# atmega_copier.net
KiCad netlist of a schematic drawn in EAGLE
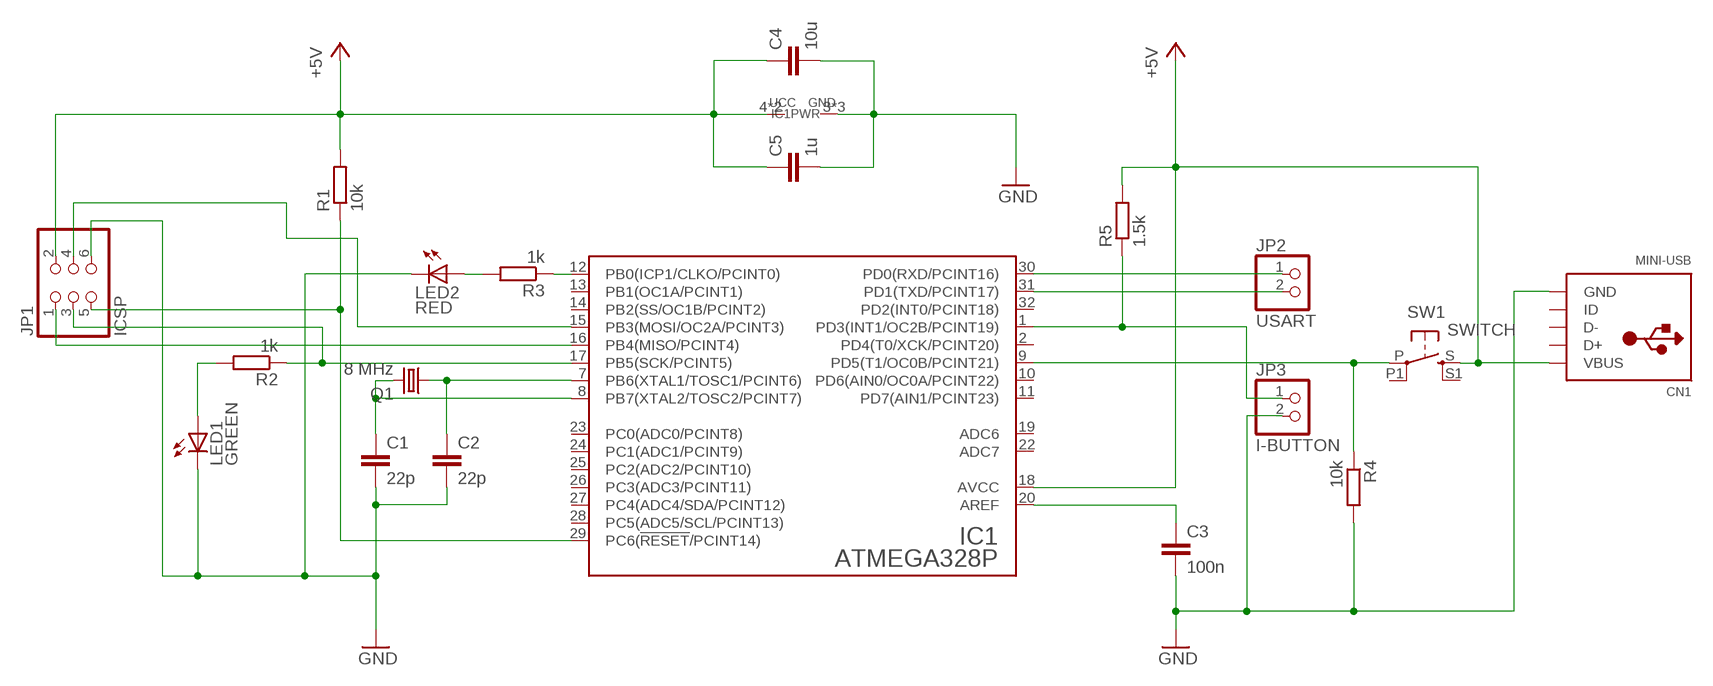
[diagram p0: schematic, sheet 1]

(export (version "E")
  (design (tool "Eeschema 10.0.6"))
  (components
    (comp (ref "C1")
      (value "22p")
      (footprint "eagle-import:C0805")
      (libsource (lib "eagle-import") (part "C-EUC0805"))
    )
    (comp (ref "C2")
      (value "22p")
      (footprint "eagle-import:C0805")
      (libsource (lib "eagle-import") (part "C-EUC0805"))
    )
    (comp (ref "C3")
      (value "100n")
      (footprint "eagle-import:C0805")
      (libsource (lib "eagle-import") (part "C-EUC0805"))
    )
    (comp (ref "C4")
      (value "10u")
      (footprint "eagle-import:C0805")
      (libsource (lib "eagle-import") (part "C-EUC0805"))
    )
    (comp (ref "C5")
      (value "1u")
      (footprint "eagle-import:C0805")
      (libsource (lib "eagle-import") (part "C-EUC0805"))
    )
    (comp (ref "CN1")
      (value "MINI-USB")
      (footprint "eagle-import:USB-MINIB")
      (libsource (lib "eagle-import") (part "USBMINIB"))
    )
    (comp (ref "IC1")
      (value "ATMEGA328P")
      (footprint "eagle-import:TQFP32-08")
      (libsource (lib "eagle-import") (part "ATMEGA48/88/168/328-AU"))
    )
    (comp (ref "JP1")
      (value "ICSP")
      (footprint "eagle-import:2X03")
      (libsource (lib "eagle-import") (part "PINHD-2X3"))
    )
    (comp (ref "JP2")
      (value "USART")
      (footprint "eagle-import:1X02")
      (libsource (lib "eagle-import") (part "PINHD-1X2"))
    )
    (comp (ref "JP3")
      (value "I-BUTTON")
      (footprint "eagle-import:1X02")
      (libsource (lib "eagle-import") (part "PINHD-1X2"))
    )
    (comp (ref "LED1")
      (value "GREEN")
      (footprint "eagle-import:SML0805")
      (libsource (lib "eagle-import") (part "LEDSML0805"))
    )
    (comp (ref "LED2")
      (value "RED")
      (footprint "eagle-import:SML0805")
      (libsource (lib "eagle-import") (part "LEDSML0805"))
    )
    (comp (ref "Q1")
      (value "8 MHz")
      (footprint "eagle-import:HC49UP")
      (libsource (lib "eagle-import") (part "CRYSTALHC49UP"))
    )
    (comp (ref "R1")
      (value "10k")
      (footprint "eagle-import:R0805")
      (libsource (lib "eagle-import") (part "R-EU_R0805"))
    )
    (comp (ref "R2")
      (value "1k")
      (footprint "eagle-import:R0805")
      (libsource (lib "eagle-import") (part "R-EU_R0805"))
    )
    (comp (ref "R3")
      (value "1k")
      (footprint "eagle-import:R0805")
      (libsource (lib "eagle-import") (part "R-EU_R0805"))
    )
    (comp (ref "R4")
      (value "10k")
      (footprint "eagle-import:R0805")
      (libsource (lib "eagle-import") (part "R-EU_R0805"))
    )
    (comp (ref "R5")
      (value "1.5k")
      (footprint "eagle-import:R0805")
      (libsource (lib "eagle-import") (part "R-EU_R0805"))
    )
    (comp (ref "SW1")
      (value "SWITCH")
      (footprint "eagle-import:BT4.5X4.5")
      (libsource (lib "eagle-import") (part "10-XX-4.5SMD"))
    )
  )
  (nets
    (net (code "1") (name "+5V") (class "Default")
      (node (ref "C4") (pin "1") (pinfunction "1_1") (pintype "passive"))
      (node (ref "C5") (pin "1") (pinfunction "1_1") (pintype "passive"))
      (node (ref "CN1") (pin "VBUS") (pinfunction "VBUS_VBUS") (pintype "power_in"))
      (node (ref "IC1") (pin "18") (pinfunction "AVCC_18") (pintype "power_in"))
      (node (ref "IC1") (pin "4") (pinfunction "UCC_4") (pintype "power_in"))
      (node (ref "IC1") (pin "6") (pinfunction "UCC_6") (pintype "power_in"))
      (node (ref "JP1") (pin "2") (pinfunction "2_2") (pintype "passive"))
      (node (ref "R1") (pin "2") (pinfunction "2_2") (pintype "passive"))
      (node (ref "R5") (pin "2") (pinfunction "2_2") (pintype "passive"))
      (node (ref "SW1") (pin "S") (pinfunction "S_S") (pintype "passive"))
    )
    (net (code "2") (name "GND") (class "Default")
      (node (ref "C1") (pin "2") (pinfunction "2_2") (pintype "passive"))
      (node (ref "C2") (pin "2") (pinfunction "2_2") (pintype "passive"))
      (node (ref "C3") (pin "2") (pinfunction "2_2") (pintype "passive"))
      (node (ref "C4") (pin "2") (pinfunction "2_2") (pintype "passive"))
      (node (ref "C5") (pin "2") (pinfunction "2_2") (pintype "passive"))
      (node (ref "CN1") (pin "GND") (pinfunction "GND_GND") (pintype "power_in"))
      (node (ref "IC1") (pin "21") (pinfunction "GND_21") (pintype "power_in"))
      (node (ref "IC1") (pin "3") (pinfunction "GND_3") (pintype "power_in"))
      (node (ref "IC1") (pin "5") (pinfunction "GND_5") (pintype "power_in"))
      (node (ref "JP1") (pin "6") (pinfunction "6_6") (pintype "passive"))
      (node (ref "JP3") (pin "2") (pinfunction "2_2") (pintype "passive"))
      (node (ref "LED1") (pin "C") (pinfunction "C_C") (pintype "passive"))
      (node (ref "LED2") (pin "C") (pinfunction "C_C") (pintype "passive"))
      (node (ref "R4") (pin "2") (pinfunction "2_2") (pintype "passive"))
    )
    (net (code "3") (name "Net-(IC1A-AREF)") (class "Default")
      (node (ref "C3") (pin "1") (pinfunction "1_1") (pintype "passive"))
      (node (ref "IC1") (pin "20") (pinfunction "AREF_20") (pintype "passive"))
    )
    (net (code "4") (name "Net-(IC1A-PB0(ICP1{slash}CLKO{slash}PCINT0))") (class "Default")
      (node (ref "IC1") (pin "12") (pinfunction "PB0(ICP1/CLKO/PCINT0)_12") (pintype "bidirectional"))
      (node (ref "R3") (pin "1") (pinfunction "1_1") (pintype "passive"))
    )
    (net (code "5") (name "Net-(IC1A-PB3(MOSI{slash}OC2A{slash}PCINT3))") (class "Default")
      (node (ref "IC1") (pin "15") (pinfunction "PB3(MOSI/OC2A/PCINT3)_15") (pintype "bidirectional"))
      (node (ref "JP1") (pin "4") (pinfunction "4_4") (pintype "passive"))
    )
    (net (code "6") (name "Net-(IC1A-PB4(MISO{slash}PCINT4))") (class "Default")
      (node (ref "IC1") (pin "16") (pinfunction "PB4(MISO/PCINT4)_16") (pintype "bidirectional"))
      (node (ref "JP1") (pin "1") (pinfunction "1_1") (pintype "passive"))
    )
    (net (code "7") (name "Net-(IC1A-PB5(SCK{slash}PCINT5))") (class "Default")
      (node (ref "IC1") (pin "17") (pinfunction "PB5(SCK/PCINT5)_17") (pintype "bidirectional"))
      (node (ref "JP1") (pin "3") (pinfunction "3_3") (pintype "passive"))
      (node (ref "R2") (pin "1") (pinfunction "1_1") (pintype "passive"))
    )
    (net (code "8") (name "Net-(IC1A-PB6(XTAL1{slash}TOSC1{slash}PCINT6))") (class "Default")
      (node (ref "C2") (pin "1") (pinfunction "1_1") (pintype "passive"))
      (node (ref "IC1") (pin "7") (pinfunction "PB6(XTAL1/TOSC1/PCINT6)_7") (pintype "bidirectional"))
      (node (ref "Q1") (pin "1") (pinfunction "1_1") (pintype "passive"))
    )
    (net (code "9") (name "Net-(IC1A-PB7(XTAL2{slash}TOSC2{slash}PCINT7))") (class "Default")
      (node (ref "C1") (pin "1") (pinfunction "1_1") (pintype "passive"))
      (node (ref "IC1") (pin "8") (pinfunction "PB7(XTAL2/TOSC2/PCINT7)_8") (pintype "bidirectional"))
      (node (ref "Q1") (pin "2") (pinfunction "2_2") (pintype "passive"))
    )
    (net (code "10") (name "Net-(IC1A-PC6(~{RESET}{slash}PCINT14))") (class "Default")
      (node (ref "IC1") (pin "29") (pinfunction "PC6(~{RESET}/PCINT14)_29") (pintype "bidirectional"))
      (node (ref "JP1") (pin "5") (pinfunction "5_5") (pintype "passive"))
      (node (ref "R1") (pin "1") (pinfunction "1_1") (pintype "passive"))
    )
    (net (code "11") (name "Net-(IC1A-PD0(RXD{slash}PCINT16))") (class "Default")
      (node (ref "IC1") (pin "30") (pinfunction "PD0(RXD/PCINT16)_30") (pintype "bidirectional"))
      (node (ref "JP2") (pin "1") (pinfunction "1_1") (pintype "passive"))
    )
    (net (code "12") (name "Net-(IC1A-PD1(TXD{slash}PCINT17))") (class "Default")
      (node (ref "IC1") (pin "31") (pinfunction "PD1(TXD/PCINT17)_31") (pintype "bidirectional"))
      (node (ref "JP2") (pin "2") (pinfunction "2_2") (pintype "passive"))
    )
    (net (code "13") (name "Net-(IC1A-PD3(INT1{slash}OC2B{slash}PCINT19))") (class "Default")
      (node (ref "IC1") (pin "1") (pinfunction "PD3(INT1/OC2B/PCINT19)_1") (pintype "bidirectional"))
      (node (ref "JP3") (pin "1") (pinfunction "1_1") (pintype "passive"))
      (node (ref "R5") (pin "1") (pinfunction "1_1") (pintype "passive"))
    )
    (net (code "14") (name "Net-(IC1A-PD5(T1{slash}OC0B{slash}PCINT21))") (class "Default")
      (node (ref "IC1") (pin "9") (pinfunction "PD5(T1/OC0B/PCINT21)_9") (pintype "bidirectional"))
      (node (ref "R4") (pin "1") (pinfunction "1_1") (pintype "passive"))
      (node (ref "SW1") (pin "P") (pinfunction "P_P") (pintype "passive"))
    )
    (net (code "15") (name "Net-(LED1-PadA)") (class "Default")
      (node (ref "LED1") (pin "A") (pinfunction "A_A") (pintype "passive"))
      (node (ref "R2") (pin "2") (pinfunction "2_2") (pintype "passive"))
    )
    (net (code "16") (name "Net-(LED2-PadA)") (class "Default")
      (node (ref "LED2") (pin "A") (pinfunction "A_A") (pintype "passive"))
      (node (ref "R3") (pin "2") (pinfunction "2_2") (pintype "passive"))
    )
    (net (code "17") (name "unconnected-(CN1-PadD+)") (class "Default")
      (node (ref "CN1") (pin "D+") (pinfunction "D+_D+") (pintype "bidirectional"))
    )
    (net (code "18") (name "unconnected-(CN1-PadD-)") (class "Default")
      (node (ref "CN1") (pin "D-") (pinfunction "D-_D-") (pintype "bidirectional"))
    )
    (net (code "19") (name "unconnected-(CN1-PadID)") (class "Default")
      (node (ref "CN1") (pin "ID") (pinfunction "ID_ID") (pintype "bidirectional"))
    )
    (net (code "20") (name "unconnected-(IC1A-ADC6-Pad19)") (class "Default")
      (node (ref "IC1") (pin "19") (pinfunction "ADC6_19") (pintype "passive"))
    )
    (net (code "21") (name "unconnected-(IC1A-ADC7-Pad22)") (class "Default")
      (node (ref "IC1") (pin "22") (pinfunction "ADC7_22") (pintype "passive"))
    )
    (net (code "22") (name "unconnected-(IC1A-PB1(OC1A{slash}PCINT1)-Pad13)") (class "Default")
      (node (ref "IC1") (pin "13") (pinfunction "PB1(OC1A/PCINT1)_13") (pintype "bidirectional"))
    )
    (net (code "23") (name "unconnected-(IC1A-PB2(SS{slash}OC1B{slash}PCINT2)-Pad14)") (class "Default")
      (node (ref "IC1") (pin "14") (pinfunction "PB2(SS/OC1B/PCINT2)_14") (pintype "bidirectional"))
    )
    (net (code "24") (name "unconnected-(IC1A-PC0(ADC0{slash}PCINT8)-Pad23)") (class "Default")
      (node (ref "IC1") (pin "23") (pinfunction "PC0(ADC0/PCINT8)_23") (pintype "bidirectional"))
    )
    (net (code "25") (name "unconnected-(IC1A-PC1(ADC1{slash}PCINT9)-Pad24)") (class "Default")
      (node (ref "IC1") (pin "24") (pinfunction "PC1(ADC1/PCINT9)_24") (pintype "bidirectional"))
    )
    (net (code "26") (name "unconnected-(IC1A-PC2(ADC2{slash}PCINT10)-Pad25)") (class "Default")
      (node (ref "IC1") (pin "25") (pinfunction "PC2(ADC2/PCINT10)_25") (pintype "bidirectional"))
    )
    (net (code "27") (name "unconnected-(IC1A-PC3(ADC3{slash}PCINT11)-Pad26)") (class "Default")
      (node (ref "IC1") (pin "26") (pinfunction "PC3(ADC3/PCINT11)_26") (pintype "bidirectional"))
    )
    (net (code "28") (name "unconnected-(IC1A-PC4(ADC4{slash}SDA{slash}PCINT12)-Pad27)") (class "Default")
      (node (ref "IC1") (pin "27") (pinfunction "PC4(ADC4/SDA/PCINT12)_27") (pintype "bidirectional"))
    )
    (net (code "29") (name "unconnected-(IC1A-PC5(ADC5{slash}SCL{slash}PCINT13)-Pad28)") (class "Default")
      (node (ref "IC1") (pin "28") (pinfunction "PC5(ADC5/SCL/PCINT13)_28") (pintype "bidirectional"))
    )
    (net (code "30") (name "unconnected-(IC1A-PD2(INT0{slash}PCINT18)-Pad32)") (class "Default")
      (node (ref "IC1") (pin "32") (pinfunction "PD2(INT0/PCINT18)_32") (pintype "bidirectional"))
    )
    (net (code "31") (name "unconnected-(IC1A-PD4(T0{slash}XCK{slash}PCINT20)-Pad2)") (class "Default")
      (node (ref "IC1") (pin "2") (pinfunction "PD4(T0/XCK/PCINT20)_2") (pintype "bidirectional"))
    )
    (net (code "32") (name "unconnected-(IC1A-PD6(AIN0{slash}OC0A{slash}PCINT22)-Pad10)") (class "Default")
      (node (ref "IC1") (pin "10") (pinfunction "PD6(AIN0/OC0A/PCINT22)_10") (pintype "bidirectional"))
    )
    (net (code "33") (name "unconnected-(IC1A-PD7(AIN1{slash}PCINT23)-Pad11)") (class "Default")
      (node (ref "IC1") (pin "11") (pinfunction "PD7(AIN1/PCINT23)_11") (pintype "bidirectional"))
    )
    (net (code "34") (name "unconnected-(SW1-PadP1)") (class "Default")
      (node (ref "SW1") (pin "P1") (pinfunction "P1_P1") (pintype "passive"))
    )
    (net (code "35") (name "unconnected-(SW1-PadS1)") (class "Default")
      (node (ref "SW1") (pin "S1") (pinfunction "S1_S1") (pintype "passive"))
    )
  )
)
